# sb-sonata-psu.net
KiCad netlist of a schematic drawn in Altium Designer
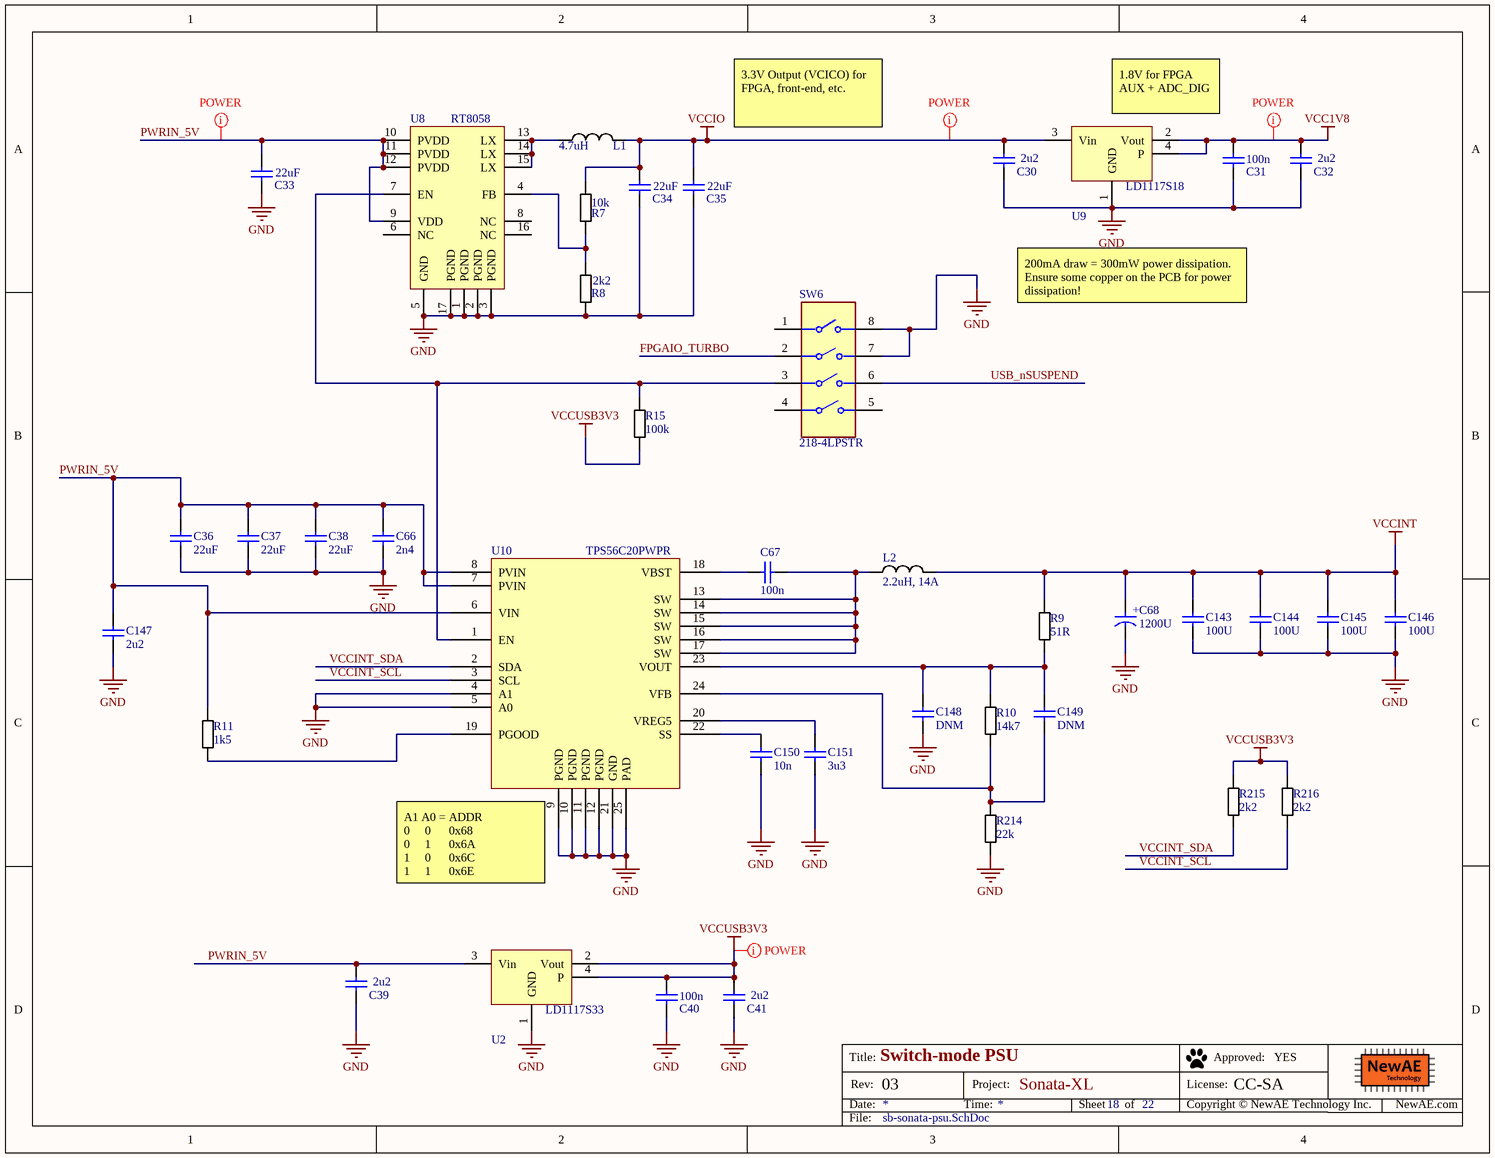
[diagram p0: sb-sonata-psu.SchDoc]

(export (version "E")
  (design (tool "Eeschema 10.0.6"))
  (components
    (comp (ref "C30")
      (value "2u2")
      (footprint "CAPC0603_M")
      (description "2u2, 0603")
      (fields (field (name "PART NUMBER") "CCHIP-2u2-0603"))
      (libsource (lib "NewAE_AltiumLib") (part "CAP"))
    )
    (comp (ref "C31")
      (value "100n")
      (footprint "CAPC0402_M")
      (description "100n, 0402")
      (fields (field (name "PART NUMBER") "CCHIP-100n-0402"))
      (libsource (lib "NewAE_AltiumLib") (part "CAP"))
    )
    (comp (ref "C32")
      (value "2u2")
      (footprint "CAPC0603_M")
      (description "2u2, 0603")
      (fields (field (name "PART NUMBER") "CCHIP-2u2-0603"))
      (libsource (lib "NewAE_AltiumLib") (part "CAP"))
    )
    (comp (ref "C33")
      (value "22uF")
      (footprint "CAPC0805_M")
      (description "22u, 16V, 0805, Ceramic")
      (fields (field (name "PART NUMBER") "CCHIP-22u-0805-16V") (field (name "TOLERANCE") "20%"))
      (libsource (lib "NewAE_AltiumLib") (part "CAP"))
    )
    (comp (ref "C34")
      (value "22uF")
      (footprint "CAPC0805_M")
      (description "22u, 16V, 0805, Ceramic")
      (fields (field (name "PART NUMBER") "CCHIP-22u-0805-16V") (field (name "TOLERANCE") "20%"))
      (libsource (lib "NewAE_AltiumLib") (part "CAP"))
    )
    (comp (ref "C35")
      (value "22uF")
      (footprint "CAPC0805_M")
      (description "22u, 16V, 0805, Ceramic")
      (fields (field (name "PART NUMBER") "CCHIP-22u-0805-16V") (field (name "TOLERANCE") "20%"))
      (libsource (lib "NewAE_AltiumLib") (part "CAP"))
    )
    (comp (ref "C36")
      (value "22uF")
      (footprint "CAPC0805_M")
      (description "22u, 16V, 0805, Ceramic")
      (fields (field (name "PART NUMBER") "CCHIP-22u-0805-16V") (field (name "TOLERANCE") "20%"))
      (libsource (lib "NewAE_AltiumLib") (part "CAP"))
    )
    (comp (ref "C37")
      (value "22uF")
      (footprint "CAPC0805_M")
      (description "22u, 16V, 0805, Ceramic")
      (fields (field (name "PART NUMBER") "CCHIP-22u-0805-16V") (field (name "TOLERANCE") "20%"))
      (libsource (lib "NewAE_AltiumLib") (part "CAP"))
    )
    (comp (ref "C38")
      (value "22uF")
      (footprint "CAPC0805_M")
      (description "22u, 16V, 0805, Ceramic")
      (fields (field (name "PART NUMBER") "CCHIP-22u-0805-16V") (field (name "TOLERANCE") "20%"))
      (libsource (lib "NewAE_AltiumLib") (part "CAP"))
    )
    (comp (ref "C39")
      (value "2u2")
      (footprint "CAPC0603_M")
      (description "2u2, 0603")
      (fields (field (name "PART NUMBER") "CCHIP-2u2-0603"))
      (libsource (lib "NewAE_AltiumLib") (part "CAP"))
    )
    (comp (ref "C40")
      (value "100n")
      (footprint "CAPC0402_M")
      (description "100n, 0402")
      (fields (field (name "PART NUMBER") "CCHIP-100n-0402"))
      (libsource (lib "NewAE_AltiumLib") (part "CAP"))
    )
    (comp (ref "C41")
      (value "2u2")
      (footprint "CAPC0603_M")
      (description "2u2, 0603")
      (fields (field (name "PART NUMBER") "CCHIP-2u2-0603"))
      (libsource (lib "NewAE_AltiumLib") (part "CAP"))
    )
    (comp (ref "C66")
      (value "2n4")
      (footprint "RESC1608X55N")
      (description "CAP CER 2400PF 50V C0G/NP0 0603")
      (fields (field (name "PART NUMBER") "CCHIP-2N4-0603-50V") (field (name "TOLERANCE") "±5%"))
      (libsource (lib "NewAE_AltiumLib") (part "CAP"))
    )
    (comp (ref "C67")
      (value "100n")
      (footprint "CAPC0603_M")
      (description "100n, 0603")
      (fields (field (name "PART NUMBER") "CCHIP-100n-0603"))
      (libsource (lib "NewAE_AltiumLib") (part "CAP"))
    )
    (comp (ref "C68")
      (value "1200U")
      (footprint "PAN_C10_POS1_NEG2")
      (description "CAP ALUM POLY 1200UF 2.5V SMD")
      (fields (field (name "PART NUMBER") "2SVPE1200M"))
      (libsource (lib "NewAE_AltiumLib") (part "CAP_POL"))
    )
    (comp (ref "C143")
      (value "100U")
      (footprint "CAPC1206_M")
      (description "CAP CER 100UF 6.3V X5R 1206")
      (fields (field (name "PART NUMBER") "CCHIP-100u-1206"))
      (libsource (lib "NewAE_AltiumLib") (part "CAP"))
    )
    (comp (ref "C144")
      (value "100U")
      (footprint "CAPC1206_M")
      (description "CAP CER 100UF 6.3V X5R 1206")
      (fields (field (name "PART NUMBER") "CCHIP-100u-1206"))
      (libsource (lib "NewAE_AltiumLib") (part "CAP"))
    )
    (comp (ref "C145")
      (value "100U")
      (footprint "CAPC1206_M")
      (description "CAP CER 100UF 6.3V X5R 1206")
      (fields (field (name "PART NUMBER") "CCHIP-100u-1206"))
      (libsource (lib "NewAE_AltiumLib") (part "CAP"))
    )
    (comp (ref "C146")
      (value "100U")
      (footprint "CAPC1206_M")
      (description "CAP CER 100UF 6.3V X5R 1206")
      (fields (field (name "PART NUMBER") "CCHIP-100u-1206"))
      (libsource (lib "NewAE_AltiumLib") (part "CAP"))
    )
    (comp (ref "C147")
      (value "2u2")
      (footprint "CAPC0603_M")
      (description "2u2, 0603")
      (fields (field (name "PART NUMBER") "CCHIP-2u2-0603-25V") (field (name "TOLERANCE") "±20%"))
      (libsource (lib "NewAE_AltiumLib") (part "CAP"))
    )
    (comp (ref "C148")
      (value "DNM")
      (footprint "CAPC0402_M")
      (description "DNM, 0402")
      (fields (field (name "PART NUMBER") "CCHIP-DNM-0402"))
      (libsource (lib "NewAE_AltiumLib") (part "CAP"))
    )
    (comp (ref "C149")
      (value "DNM")
      (footprint "CAPC0402_M")
      (description "DNM, 0402")
      (fields (field (name "PART NUMBER") "CCHIP-DNM-0402"))
      (libsource (lib "NewAE_AltiumLib") (part "CAP"))
    )
    (comp (ref "C150")
      (value "10n")
      (footprint "CAPC0603_M")
      (description "10n, 0603")
      (fields (field (name "PART NUMBER") "CCHIP-10n-0603"))
      (libsource (lib "NewAE_AltiumLib") (part "CAP"))
    )
    (comp (ref "C151")
      (value "3u3")
      (footprint "CAPC0603_M")
      (description "3u3, 0603")
      (fields (field (name "PART NUMBER") "CCHIP-3u3-0603"))
      (libsource (lib "NewAE_AltiumLib") (part "CAP"))
    )
    (comp (ref "L1")
      (value "4.7uH")
      (footprint "NR6028")
      (description "fixed ind, ferrite, shielded")
      (fields (field (name "PART NUMBER") "NR6028T4R7M"))
      (libsource (lib "NewAE_AltiumLib") (part "IND"))
    )
    (comp (ref "L2")
      (value "2.2uH, 14A")
      (footprint "XAL1060-222")
      (description "2.2uH, 14A RMS")
      (fields (field (name "PART NUMBER") "XAL1060-222MEB"))
      (libsource (lib "NewAE_AltiumLib") (part "IND"))
    )
    (comp (ref "R7")
      (value "10k")
      (footprint "RESC1005X40N")
      (description "10k res, 0402, 1%, 1/16W")
      (fields (field (name "PART NUMBER") "RCHIP-10K-0402") (field (name "TOLERANCE") "1%"))
      (libsource (lib "NewAE_AltiumLib") (part "RES-EU"))
    )
    (comp (ref "R8")
      (value "2k2")
      (footprint "RESC1005X40N")
      (description "2k2 res, 0402, 1%, 1/16W")
      (fields (field (name "PART NUMBER") "RCHIP-2K2-0402") (field (name "TOLERANCE") "1%"))
      (libsource (lib "NewAE_AltiumLib") (part "RES-EU"))
    )
    (comp (ref "R9")
      (value "51R")
      (footprint "RESC1608X55N")
      (description "51R res, 0603, 1%, 1/10W")
      (fields (field (name "PART NUMBER") "RCHIP-51R-0603") (field (name "TOLERANCE") "1%"))
      (libsource (lib "NewAE_AltiumLib") (part "RES-EU"))
    )
    (comp (ref "R10")
      (value "14k7")
      (footprint "RESC1005X40N")
      (description "14k7 res, 0402, 1%, 1/16W")
      (fields (field (name "PART NUMBER") "RCHIP-14K7-0402") (field (name "TOLERANCE") "1%"))
      (libsource (lib "NewAE_AltiumLib") (part "RES-EU"))
    )
    (comp (ref "R11")
      (value "1k5")
      (footprint "RESC1608X55N")
      (description "1k5 res, 0603, 1%, 1/10W")
      (fields (field (name "PART NUMBER") "RCHIP-1K5-0603") (field (name "TOLERANCE") "1%"))
      (libsource (lib "") (part "RES-EU_1"))
    )
    (comp (ref "R15")
      (value "100k")
      (footprint "RESC1608X55N")
      (description "100k res, 0603, 1%, 1/10W")
      (fields (field (name "PART NUMBER") "RCHIP-100K-0603") (field (name "TOLERANCE") "1%"))
      (libsource (lib "") (part "RES-EU_1"))
    )
    (comp (ref "R214")
      (value "22k")
      (footprint "RESC1005X40N")
      (description "22k res, 0402, 1%, 1/16W")
      (fields (field (name "PART NUMBER") "RCHIP-22K-0402") (field (name "TOLERANCE") "1%"))
      (libsource (lib "NewAE_AltiumLib") (part "RES-EU"))
    )
    (comp (ref "R215")
      (value "2k2")
      (footprint "RESC1005X40N")
      (description "2k2 res, 0402, 1%, 1/16W")
      (fields (field (name "PART NUMBER") "RCHIP-2K2-0402") (field (name "TOLERANCE") "1%"))
      (libsource (lib "NewAE_AltiumLib") (part "RES-EU"))
    )
    (comp (ref "R216")
      (value "2k2")
      (footprint "RESC1005X40N")
      (description "2k2 res, 0402, 1%, 1/16W")
      (fields (field (name "PART NUMBER") "RCHIP-2K2-0402") (field (name "TOLERANCE") "1%"))
      (libsource (lib "NewAE_AltiumLib") (part "RES-EU"))
    )
    (comp (ref "SW6")
      (value "218-4LPSTR")
      (footprint "FP-218-4LPSTR-MFG")
      (description "SWITCH SLIDE DIP SPST 25MA 24V")
      (libsource (lib "Altium Content Vault") (part "a78650ae27aee94b64e9c93150c7d5d"))
    )
    (comp (ref "U2")
      (value "LD1117S33")
      (footprint "SOT-223")
      (description "IC REG LIN POS 3.3V 800MA SOT223")
      (libsource (lib "NewAE_AltiumLib") (part "LD1117S33"))
    )
    (comp (ref "U8")
      (value "RT8058")
      (footprint "QFN16_50P300X300X100_HS-17M")
      (description "Switching supply controller, 2A")
      (libsource (lib "NewAE_AltiumLib") (part "RT8058"))
    )
    (comp (ref "U9")
      (value "LD1117S18")
      (footprint "SOT-223")
      (description "IC REG LIN POS 1.8V 800MA SOT223")
      (libsource (lib "NewAE_AltiumLib") (part "LD1117S33"))
    )
    (comp (ref "U10")
      (value "TPS56C20PWPR")
      (footprint "R-PDSO-G24")
      (description "IC Reg Buck Adj/Prog 12A")
      (libsource (lib "NewAE_AltiumLib") (part "TPS56C20PWPR"))
    )
  )
  (nets
    (net (code "1") (name "/FPGAIO_TURBO") (class "Default")
      (node (ref "SW6") (pin "2") (pinfunction "2_2") (pintype "passive"))
    )
    (net (code "2") (name "/PWRIN_5V") (class "Default")
      (node (ref "C147") (pin "1") (pinfunction "1_1") (pintype "passive"))
      (node (ref "C33") (pin "1") (pinfunction "1_1") (pintype "passive"))
      (node (ref "C36") (pin "1") (pinfunction "1_1") (pintype "passive"))
      (node (ref "C37") (pin "1") (pinfunction "1_1") (pintype "passive"))
      (node (ref "C38") (pin "1") (pinfunction "1_1") (pintype "passive"))
      (node (ref "C39") (pin "1") (pinfunction "1_1") (pintype "passive"))
      (node (ref "C66") (pin "1") (pinfunction "1_1") (pintype "passive"))
      (node (ref "R11") (pin "2") (pinfunction "2_2") (pintype "passive"))
      (node (ref "U10") (pin "6") (pinfunction "VIN_6") (pintype "passive"))
      (node (ref "U10") (pin "7") (pinfunction "PVIN_7") (pintype "passive"))
      (node (ref "U10") (pin "8") (pinfunction "PVIN_8") (pintype "passive"))
      (node (ref "U2") (pin "3") (pinfunction "Vin_3") (pintype "passive"))
      (node (ref "U8") (pin "10") (pinfunction "PVDD_10") (pintype "passive"))
      (node (ref "U8") (pin "11") (pinfunction "PVDD_11") (pintype "passive"))
      (node (ref "U8") (pin "12") (pinfunction "PVDD_12") (pintype "passive"))
      (node (ref "U8") (pin "9") (pinfunction "VDD_9") (pintype "passive"))
    )
    (net (code "3") (name "/USB_nSUSPEND") (class "Default")
      (node (ref "SW6") (pin "6") (pinfunction "6_6") (pintype "passive"))
    )
    (net (code "4") (name "/VCCINT_SCL") (class "Default")
      (node (ref "R216") (pin "2") (pinfunction "2_2") (pintype "passive"))
      (node (ref "U10") (pin "3") (pinfunction "SCL_3") (pintype "passive"))
    )
    (net (code "5") (name "/VCCINT_SDA") (class "Default")
      (node (ref "R215") (pin "2") (pinfunction "2_2") (pintype "passive"))
      (node (ref "U10") (pin "2") (pinfunction "SDA_2") (pintype "passive"))
    )
    (net (code "6") (name "GND") (class "Default")
      (node (ref "C143") (pin "2") (pinfunction "2_2") (pintype "passive"))
      (node (ref "C144") (pin "2") (pinfunction "2_2") (pintype "passive"))
      (node (ref "C145") (pin "2") (pinfunction "2_2") (pintype "passive"))
      (node (ref "C146") (pin "2") (pinfunction "2_2") (pintype "passive"))
      (node (ref "C147") (pin "2") (pinfunction "2_2") (pintype "passive"))
      (node (ref "C148") (pin "2") (pinfunction "2_2") (pintype "passive"))
      (node (ref "C150") (pin "2") (pinfunction "2_2") (pintype "passive"))
      (node (ref "C151") (pin "2") (pinfunction "2_2") (pintype "passive"))
      (node (ref "C30") (pin "2") (pinfunction "2_2") (pintype "passive"))
      (node (ref "C31") (pin "2") (pinfunction "2_2") (pintype "passive"))
      (node (ref "C32") (pin "2") (pinfunction "2_2") (pintype "passive"))
      (node (ref "C33") (pin "2") (pinfunction "2_2") (pintype "passive"))
      (node (ref "C34") (pin "2") (pinfunction "2_2") (pintype "passive"))
      (node (ref "C35") (pin "2") (pinfunction "2_2") (pintype "passive"))
      (node (ref "C36") (pin "2") (pinfunction "2_2") (pintype "passive"))
      (node (ref "C37") (pin "2") (pinfunction "2_2") (pintype "passive"))
      (node (ref "C38") (pin "2") (pinfunction "2_2") (pintype "passive"))
      (node (ref "C39") (pin "2") (pinfunction "2_2") (pintype "passive"))
      (node (ref "C40") (pin "2") (pinfunction "2_2") (pintype "passive"))
      (node (ref "C41") (pin "2") (pinfunction "2_2") (pintype "passive"))
      (node (ref "C66") (pin "2") (pinfunction "2_2") (pintype "passive"))
      (node (ref "C68") (pin "2") (pinfunction "2_2") (pintype "passive"))
      (node (ref "R214") (pin "2") (pinfunction "2_2") (pintype "passive"))
      (node (ref "R8") (pin "2") (pinfunction "2_2") (pintype "passive"))
      (node (ref "SW6") (pin "7") (pinfunction "7_7") (pintype "passive"))
      (node (ref "SW6") (pin "8") (pinfunction "8_8") (pintype "passive"))
      (node (ref "U10") (pin "10") (pinfunction "PGND_10") (pintype "passive"))
      (node (ref "U10") (pin "11") (pinfunction "PGND_11") (pintype "passive"))
      (node (ref "U10") (pin "12") (pinfunction "PGND_12") (pintype "passive"))
      (node (ref "U10") (pin "21") (pinfunction "GND_21") (pintype "passive"))
      (node (ref "U10") (pin "25") (pinfunction "PAD_25") (pintype "passive"))
      (node (ref "U10") (pin "4") (pinfunction "A1_4") (pintype "passive"))
      (node (ref "U10") (pin "5") (pinfunction "A0_5") (pintype "passive"))
      (node (ref "U10") (pin "9") (pinfunction "PGND_9") (pintype "passive"))
      (node (ref "U2") (pin "1") (pinfunction "GND_1") (pintype "passive"))
      (node (ref "U8") (pin "1") (pinfunction "PGND_1") (pintype "passive"))
      (node (ref "U8") (pin "17") (pinfunction "PGND_17") (pintype "passive"))
      (node (ref "U8") (pin "2") (pinfunction "PGND_2") (pintype "passive"))
      (node (ref "U8") (pin "3") (pinfunction "PGND_3") (pintype "passive"))
      (node (ref "U8") (pin "5") (pinfunction "GND_5") (pintype "passive"))
      (node (ref "U9") (pin "1") (pinfunction "GND_1") (pintype "passive"))
    )
    (net (code "7") (name "Net-(C67-Pad2)") (class "Default")
      (node (ref "C67") (pin "2") (pinfunction "2_2") (pintype "passive"))
      (node (ref "L2") (pin "1") (pinfunction "1_1") (pintype "passive"))
      (node (ref "U10") (pin "13") (pinfunction "SW_13") (pintype "passive"))
      (node (ref "U10") (pin "14") (pinfunction "SW_14") (pintype "passive"))
      (node (ref "U10") (pin "15") (pinfunction "SW_15") (pintype "passive"))
      (node (ref "U10") (pin "16") (pinfunction "SW_16") (pintype "passive"))
      (node (ref "U10") (pin "17") (pinfunction "SW_17") (pintype "passive"))
    )
    (net (code "8") (name "Net-(L1-Pad1)") (class "Default")
      (node (ref "L1") (pin "1") (pinfunction "1_1") (pintype "passive"))
      (node (ref "U8") (pin "13") (pinfunction "LX_13") (pintype "passive"))
      (node (ref "U8") (pin "14") (pinfunction "LX_14") (pintype "passive"))
      (node (ref "U8") (pin "15") (pinfunction "LX_15") (pintype "passive"))
    )
    (net (code "9") (name "Net-(U8-FB)") (class "Default")
      (node (ref "R7") (pin "2") (pinfunction "2_2") (pintype "passive"))
      (node (ref "R8") (pin "1") (pinfunction "1_1") (pintype "passive"))
      (node (ref "U8") (pin "4") (pinfunction "FB_4") (pintype "passive"))
    )
    (net (code "10") (name "Net-(U10-EN)") (class "Default")
      (node (ref "R15") (pin "2") (pinfunction "2_2") (pintype "passive"))
      (node (ref "SW6") (pin "3") (pinfunction "3_3") (pintype "passive"))
      (node (ref "U10") (pin "1") (pinfunction "EN_1") (pintype "passive"))
      (node (ref "U8") (pin "7") (pinfunction "EN_7") (pintype "passive"))
    )
    (net (code "11") (name "Net-(U10-PGOOD)") (class "Default")
      (node (ref "R11") (pin "1") (pinfunction "1_1") (pintype "passive"))
      (node (ref "U10") (pin "19") (pinfunction "PGOOD_19") (pintype "passive"))
    )
    (net (code "12") (name "Net-(U10-SS)") (class "Default")
      (node (ref "C150") (pin "1") (pinfunction "1_1") (pintype "passive"))
      (node (ref "U10") (pin "22") (pinfunction "SS_22") (pintype "passive"))
    )
    (net (code "13") (name "Net-(U10-VBST)") (class "Default")
      (node (ref "C67") (pin "1") (pinfunction "1_1") (pintype "passive"))
      (node (ref "U10") (pin "18") (pinfunction "VBST_18") (pintype "passive"))
    )
    (net (code "14") (name "Net-(U10-VFB)") (class "Default")
      (node (ref "C149") (pin "2") (pinfunction "2_2") (pintype "passive"))
      (node (ref "R10") (pin "2") (pinfunction "2_2") (pintype "passive"))
      (node (ref "R214") (pin "1") (pinfunction "1_1") (pintype "passive"))
      (node (ref "U10") (pin "24") (pinfunction "VFB_24") (pintype "passive"))
    )
    (net (code "15") (name "Net-(U10-VOUT)") (class "Default")
      (node (ref "C148") (pin "1") (pinfunction "1_1") (pintype "passive"))
      (node (ref "C149") (pin "1") (pinfunction "1_1") (pintype "passive"))
      (node (ref "R10") (pin "1") (pinfunction "1_1") (pintype "passive"))
      (node (ref "R9") (pin "2") (pinfunction "2_2") (pintype "passive"))
      (node (ref "U10") (pin "23") (pinfunction "VOUT_23") (pintype "passive"))
    )
    (net (code "16") (name "Net-(U10-VREG5)") (class "Default")
      (node (ref "C151") (pin "1") (pinfunction "1_1") (pintype "passive"))
      (node (ref "U10") (pin "20") (pinfunction "VREG5_20") (pintype "passive"))
    )
    (net (code "17") (name "VCC1V8") (class "Default")
      (node (ref "C31") (pin "1") (pinfunction "1_1") (pintype "passive"))
      (node (ref "C32") (pin "1") (pinfunction "1_1") (pintype "passive"))
      (node (ref "U9") (pin "2") (pinfunction "Vout_2") (pintype "passive"))
      (node (ref "U9") (pin "4") (pinfunction "P_4") (pintype "passive"))
    )
    (net (code "18") (name "VCCINT") (class "Default")
      (node (ref "C143") (pin "1") (pinfunction "1_1") (pintype "passive"))
      (node (ref "C144") (pin "1") (pinfunction "1_1") (pintype "passive"))
      (node (ref "C145") (pin "1") (pinfunction "1_1") (pintype "passive"))
      (node (ref "C146") (pin "1") (pinfunction "1_1") (pintype "passive"))
      (node (ref "C68") (pin "1") (pinfunction "1_1") (pintype "passive"))
      (node (ref "L2") (pin "2") (pinfunction "2_2") (pintype "passive"))
      (node (ref "R9") (pin "1") (pinfunction "1_1") (pintype "passive"))
    )
    (net (code "19") (name "VCCIO") (class "Default")
      (node (ref "C30") (pin "1") (pinfunction "1_1") (pintype "passive"))
      (node (ref "C34") (pin "1") (pinfunction "1_1") (pintype "passive"))
      (node (ref "C35") (pin "1") (pinfunction "1_1") (pintype "passive"))
      (node (ref "L1") (pin "2") (pinfunction "2_2") (pintype "passive"))
      (node (ref "R7") (pin "1") (pinfunction "1_1") (pintype "passive"))
      (node (ref "U9") (pin "3") (pinfunction "Vin_3") (pintype "passive"))
    )
    (net (code "20") (name "VCCUSB3V3") (class "Default")
      (node (ref "C40") (pin "1") (pinfunction "1_1") (pintype "passive"))
      (node (ref "C41") (pin "1") (pinfunction "1_1") (pintype "passive"))
      (node (ref "R15") (pin "1") (pinfunction "1_1") (pintype "passive"))
      (node (ref "R215") (pin "1") (pinfunction "1_1") (pintype "passive"))
      (node (ref "R216") (pin "1") (pinfunction "1_1") (pintype "passive"))
      (node (ref "U2") (pin "2") (pinfunction "Vout_2") (pintype "passive"))
      (node (ref "U2") (pin "4") (pinfunction "P_4") (pintype "passive"))
    )
    (net (code "21") (name "unconnected-(SW6-Pad1)") (class "Default")
      (node (ref "SW6") (pin "1") (pinfunction "1_1") (pintype "passive"))
    )
    (net (code "22") (name "unconnected-(SW6-Pad4)") (class "Default")
      (node (ref "SW6") (pin "4") (pinfunction "4_4") (pintype "passive"))
    )
    (net (code "23") (name "unconnected-(SW6-Pad5)") (class "Default")
      (node (ref "SW6") (pin "5") (pinfunction "5_5") (pintype "passive"))
    )
    (net (code "24") (name "unconnected-(U8-NC-Pad6)") (class "Default")
      (node (ref "U8") (pin "6") (pinfunction "NC_6") (pintype "passive"))
    )
    (net (code "25") (name "unconnected-(U8-NC-Pad8)") (class "Default")
      (node (ref "U8") (pin "8") (pinfunction "NC_8") (pintype "passive"))
    )
    (net (code "26") (name "unconnected-(U8-NC-Pad16)") (class "Default")
      (node (ref "U8") (pin "16") (pinfunction "NC_16") (pintype "passive"))
    )
  )
)
